# Laser_Array_CPU_V1_4.net
KiCad netlist of a schematic drawn in EAGLE
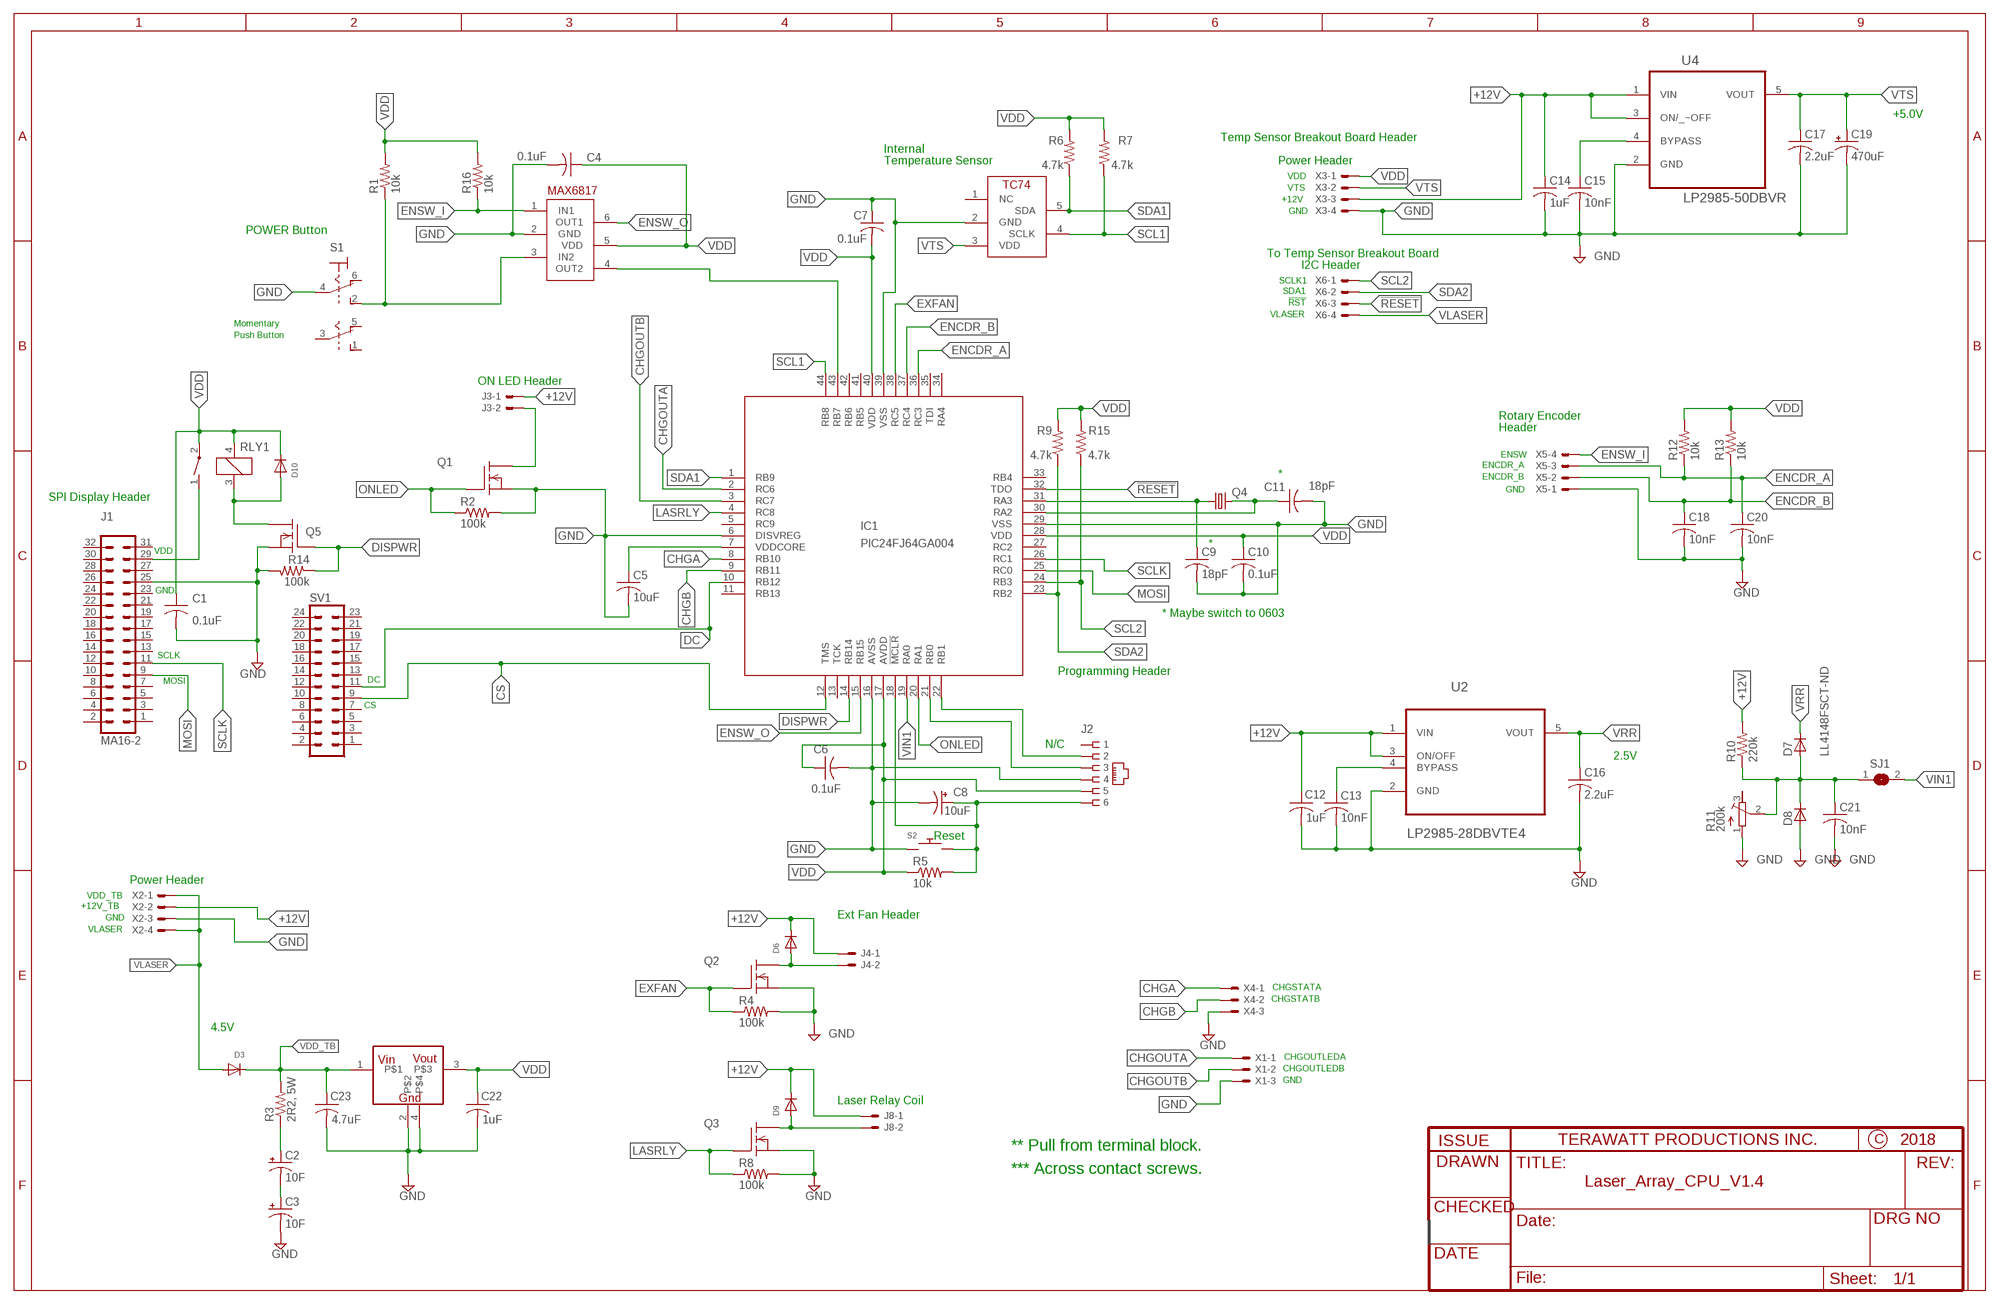
[diagram p0: schematic, sheet 1]

(export (version "E")
  (design (tool "Eeschema 10.0.6"))
  (components
    (comp (ref "C1")
      (value "0.1uF")
      (footprint "eagle-import:C0805")
      (libsource (lib "eagle-import") (part "C-USC0805"))
    )
    (comp (ref "C2")
      (value "10F")
      (footprint "eagle-import:E5-10,5")
      (libsource (lib "eagle-import") (part "CPOL-USE5-10.5"))
    )
    (comp (ref "C3")
      (value "10F")
      (footprint "eagle-import:E5-10,5")
      (libsource (lib "eagle-import") (part "CPOL-USE5-10.5"))
    )
    (comp (ref "C4")
      (value "0.1uF")
      (footprint "eagle-import:C0805")
      (libsource (lib "eagle-import") (part "C-USC0805"))
    )
    (comp (ref "C5")
      (value "10uF")
      (footprint "eagle-import:C0805")
      (libsource (lib "eagle-import") (part "C-USC0805"))
    )
    (comp (ref "C6")
      (value "0.1uF")
      (footprint "eagle-import:C0805")
      (libsource (lib "eagle-import") (part "C-USC0805"))
    )
    (comp (ref "C7")
      (value "0.1uF")
      (footprint "eagle-import:C0805")
      (libsource (lib "eagle-import") (part "C-USC0805"))
    )
    (comp (ref "C8")
      (value "10uF")
      (footprint "eagle-import:CAP3X3")
      (libsource (lib "eagle-import") (part "CAP3X3"))
    )
    (comp (ref "C9")
      (value "18pF")
      (footprint "eagle-import:C0805")
      (libsource (lib "eagle-import") (part "C-USC0805"))
    )
    (comp (ref "C10")
      (value "0.1uF")
      (footprint "eagle-import:C0805")
      (libsource (lib "eagle-import") (part "C-USC0805"))
    )
    (comp (ref "C11")
      (value "18pF")
      (footprint "eagle-import:C0805")
      (libsource (lib "eagle-import") (part "C-USC0805"))
    )
    (comp (ref "C12")
      (value "1uF")
      (footprint "eagle-import:C0805")
      (libsource (lib "eagle-import") (part "C-USC0805"))
    )
    (comp (ref "C13")
      (value "10nF")
      (footprint "eagle-import:C0805")
      (libsource (lib "eagle-import") (part "C-USC0805"))
    )
    (comp (ref "C14")
      (value "1uF")
      (footprint "eagle-import:C0805")
      (libsource (lib "eagle-import") (part "C-USC0805"))
    )
    (comp (ref "C15")
      (value "10nF")
      (footprint "eagle-import:C0805")
      (libsource (lib "eagle-import") (part "C-USC0805"))
    )
    (comp (ref "C16")
      (value "2.2uF")
      (footprint "eagle-import:C0805")
      (libsource (lib "eagle-import") (part "C-USC0805"))
    )
    (comp (ref "C17")
      (value "2.2uF")
      (footprint "eagle-import:C0805")
      (libsource (lib "eagle-import") (part "C-USC0805"))
    )
    (comp (ref "C18")
      (value "10nF")
      (footprint "eagle-import:C0805")
      (libsource (lib "eagle-import") (part "C-USC0805"))
    )
    (comp (ref "C19")
      (value "470uF")
      (footprint "eagle-import:PANASONIC_F")
      (libsource (lib "eagle-import") (part "CPOL-USF"))
    )
    (comp (ref "C20")
      (value "10nF")
      (footprint "eagle-import:C0805")
      (libsource (lib "eagle-import") (part "C-USC0805"))
    )
    (comp (ref "C21")
      (value "10nF")
      (footprint "eagle-import:C0805")
      (libsource (lib "eagle-import") (part "C-USC0805"))
    )
    (comp (ref "C22")
      (value "1uF")
      (footprint "eagle-import:C0805")
      (libsource (lib "eagle-import") (part "C-USC0805"))
    )
    (comp (ref "C23")
      (value "4.7uF")
      (footprint "eagle-import:C0805")
      (libsource (lib "eagle-import") (part "C-USC0805"))
    )
    (comp (ref "D3")
      (value "S10M-TPMSCT_ND")
      (footprint "eagle-import:S10M-TPMSCT-ND")
      (libsource (lib "eagle-import") (part "S10M-TPMSCT_ND"))
    )
    (comp (ref "D6")
      (value "DIODE_GENPURP_1A_100V")
      (footprint "eagle-import:DO214AC")
      (libsource (lib "eagle-import") (part "DIODE_GENPURP_1A_100V"))
    )
    (comp (ref "D7")
      (value "LL4148FSCT-ND")
      (footprint "eagle-import:SOD80")
      (libsource (lib "eagle-import") (part "D-SOD-80"))
    )
    (comp (ref "D8")
      (value "LL4148FSCT-ND")
      (footprint "eagle-import:SOD80")
      (libsource (lib "eagle-import") (part "D-SOD-80"))
    )
    (comp (ref "D9")
      (value "DIODE_GENPURP_1A_100V")
      (footprint "eagle-import:DO214AC")
      (libsource (lib "eagle-import") (part "DIODE_GENPURP_1A_100V"))
    )
    (comp (ref "D10")
      (value "DIODE_GENPURP_1A_100V")
      (footprint "eagle-import:DO214AC")
      (libsource (lib "eagle-import") (part "DIODE_GENPURP_1A_100V"))
    )
    (comp (ref "IC1")
      (value "PIC24FJ64GA004")
      (footprint "eagle-import:TQFP44")
      (fields (field (name "MPN") "PIC24FJ64GA004-E/PT"))
      (libsource (lib "eagle-import") (part "PIC24FJ64GA004"))
    )
    (comp (ref "J1")
      (value "MA16-2")
      (footprint "eagle-import:MA16-2")
      (libsource (lib "eagle-import") (part "MA16-2"))
    )
    (comp (ref "J2")
      (value "RJ_25")
      (footprint "eagle-import:RJ11-NO_SHIELD")
      (libsource (lib "eagle-import") (part "RJ_25"))
    )
    (comp (ref "J3")
      (value "22-23-2021")
      (footprint "eagle-import:22-23-2021")
      (fields (field (name "MF") "MOLEX"))
      (libsource (lib "eagle-import") (part "22-23-2021"))
    )
    (comp (ref "J4")
      (value "22-23-2021")
      (footprint "eagle-import:22-23-2021")
      (fields (field (name "MF") "MOLEX"))
      (libsource (lib "eagle-import") (part "22-23-2021"))
    )
    (comp (ref "J8")
      (value "22-23-2021")
      (footprint "eagle-import:22-23-2021")
      (fields (field (name "MF") "MOLEX"))
      (libsource (lib "eagle-import") (part "22-23-2021"))
    )
    (comp (ref "Q1")
      (value "QS5U34CT-ND_MOSFET_N_CHANNEL")
      (footprint "eagle-import:SOT23-5L")
      (libsource (lib "eagle-import") (part "QS5U34CT-ND_MOSFET_N_CHANNEL"))
    )
    (comp (ref "Q2")
      (value "QS5U34CT-ND_MOSFET_N_CHANNEL")
      (footprint "eagle-import:SOT23-5L")
      (libsource (lib "eagle-import") (part "QS5U34CT-ND_MOSFET_N_CHANNEL"))
    )
    (comp (ref "Q3")
      (value "QS5U34CT-ND_MOSFET_N_CHANNEL")
      (footprint "eagle-import:SOT23-5L")
      (libsource (lib "eagle-import") (part "QS5U34CT-ND_MOSFET_N_CHANNEL"))
    )
    (comp (ref "Q4")
      (value "CRYSTALSM49")
      (footprint "eagle-import:SM49")
      (libsource (lib "eagle-import") (part "CRYSTALSM49"))
    )
    (comp (ref "Q5")
      (value "QS5U34CT-ND_MOSFET_N_CHANNEL")
      (footprint "eagle-import:SOT23-5L")
      (libsource (lib "eagle-import") (part "QS5U34CT-ND_MOSFET_N_CHANNEL"))
    )
    (comp (ref "R1")
      (value "10k")
      (footprint "eagle-import:R0805")
      (libsource (lib "eagle-import") (part "R-US_R0805"))
    )
    (comp (ref "R2")
      (value "100k")
      (footprint "eagle-import:R0805")
      (libsource (lib "eagle-import") (part "R-US_R0805"))
    )
    (comp (ref "R3")
      (value "2R2, 5W")
      (footprint "eagle-import:RESISTOR5W")
      (libsource (lib "eagle-import") (part "RESISTOR5W"))
    )
    (comp (ref "R4")
      (value "100k")
      (footprint "eagle-import:R0805")
      (libsource (lib "eagle-import") (part "R-US_R0805"))
    )
    (comp (ref "R5")
      (value "10k")
      (footprint "eagle-import:R0805")
      (libsource (lib "eagle-import") (part "R-US_R0805"))
    )
    (comp (ref "R6")
      (value "4.7k")
      (footprint "eagle-import:M0805")
      (libsource (lib "eagle-import") (part "R-US_M0805"))
    )
    (comp (ref "R7")
      (value "4.7k")
      (footprint "eagle-import:M0805")
      (libsource (lib "eagle-import") (part "R-US_M0805"))
    )
    (comp (ref "R8")
      (value "100k")
      (footprint "eagle-import:R0805")
      (libsource (lib "eagle-import") (part "R-US_R0805"))
    )
    (comp (ref "R9")
      (value "4.7k")
      (footprint "eagle-import:M0805")
      (libsource (lib "eagle-import") (part "R-US_M0805"))
    )
    (comp (ref "R10")
      (value "220k")
      (footprint "eagle-import:M0805")
      (libsource (lib "eagle-import") (part "R-US_M0805"))
    )
    (comp (ref "R11")
      (value "200k")
      (footprint "eagle-import:RTRIM3224X")
      (libsource (lib "eagle-import") (part "R-TRIMM3224X"))
    )
    (comp (ref "R12")
      (value "10k")
      (footprint "eagle-import:M0805")
      (libsource (lib "eagle-import") (part "R-US_M0805"))
    )
    (comp (ref "R13")
      (value "10k")
      (footprint "eagle-import:M0805")
      (libsource (lib "eagle-import") (part "R-US_M0805"))
    )
    (comp (ref "R14")
      (value "100k")
      (footprint "eagle-import:R0805")
      (libsource (lib "eagle-import") (part "R-US_R0805"))
    )
    (comp (ref "R15")
      (value "4.7k")
      (footprint "eagle-import:M0805")
      (libsource (lib "eagle-import") (part "R-US_M0805"))
    )
    (comp (ref "R16")
      (value "10k")
      (footprint "eagle-import:R0805")
      (libsource (lib "eagle-import") (part "R-US_R0805"))
    )
    (comp (ref "RLY1")
      (value "RELAY_SPST_1A")
      (footprint "eagle-import:RELAY_SPST_1A")
      (libsource (lib "eagle-import") (part "RELAY_SPST_1A"))
    )
    (comp (ref "S1")
      (value "DPDT_TOGGLE")
      (footprint "eagle-import:22-23-2061")
      (libsource (lib "eagle-import") (part "DPDT_TOGGLE"))
    )
    (comp (ref "S2")
      (value "TACT_PB")
      (footprint "eagle-import:PUSHBUTTON_SMD_SJ")
      (libsource (lib "eagle-import") (part "TACT_PB"))
    )
    (comp (ref "S3")
      (value "TC74")
      (footprint "eagle-import:SOT23-5L")
      (libsource (lib "eagle-import") (part "TC74"))
    )
    (comp (ref "SJ1") (value "SJ") (footprint "eagle-import:SJ") (libsource (lib "eagle-import") (part "SJ")))
    (comp (ref "SV1")
      (value "MA12-2")
      (footprint "eagle-import:MA12-2")
      (libsource (lib "eagle-import") (part "MA12-2"))
    )
    (comp (ref "U1")
      (value "MAX6817")
      (footprint "eagle-import:SOT23-6")
      (libsource (lib "eagle-import") (part "MAX6817"))
    )
    (comp (ref "U2")
      (value "LP2985-28DBVTE4")
      (footprint "eagle-import:SOT95P280X145-5N")
      (libsource (lib "eagle-import") (part "LP2985-28DBVTE4"))
    )
    (comp (ref "U3")
      (value "V_REG_3.0V_1.0A")
      (footprint "eagle-import:SOT223")
      (libsource (lib "eagle-import") (part "V_REG_3.0V_1.0A"))
    )
    (comp (ref "U4")
      (value "LP2985-50DBVR")
      (footprint "eagle-import:SOT95P280X145-5N")
      (fields (field (name "MPN") "LP2985-33DBVT"))
      (libsource (lib "eagle-import") (part "LP2985-50DBVR"))
    )
    (comp (ref "X1")
      (value "22-23-2031")
      (footprint "eagle-import:22-23-2031")
      (fields (field (name "MF") "MOLEX"))
      (libsource (lib "eagle-import") (part "22-23-2031"))
    )
    (comp (ref "X2")
      (value "22-23-2041")
      (footprint "eagle-import:22-23-2041")
      (fields (field (name "MF") "MOLEX"))
      (libsource (lib "eagle-import") (part "22-23-2041"))
    )
    (comp (ref "X3")
      (value "22-23-2041")
      (footprint "eagle-import:22-23-2041")
      (fields (field (name "MF") "MOLEX"))
      (libsource (lib "eagle-import") (part "22-23-2041"))
    )
    (comp (ref "X4")
      (value "22-23-2031")
      (footprint "eagle-import:22-23-2031")
      (fields (field (name "MF") "MOLEX"))
      (libsource (lib "eagle-import") (part "22-23-2031"))
    )
    (comp (ref "X5")
      (value "22-23-2041")
      (footprint "eagle-import:22-23-2041")
      (fields (field (name "MF") "MOLEX"))
      (libsource (lib "eagle-import") (part "22-23-2041"))
    )
    (comp (ref "X6")
      (value "22-23-2041")
      (footprint "eagle-import:22-23-2041")
      (fields (field (name "MF") "MOLEX"))
      (libsource (lib "eagle-import") (part "22-23-2041"))
    )
  )
  (nets
    (net (code "1") (name "+12V") (class "Default")
      (node (ref "C12") (pin "1") (pinfunction "1_1") (pintype "passive"))
      (node (ref "C14") (pin "1") (pinfunction "1_1") (pintype "passive"))
      (node (ref "D6") (pin "C") (pinfunction "C_C") (pintype "passive"))
      (node (ref "D9") (pin "C") (pinfunction "C_C") (pintype "passive"))
      (node (ref "J3") (pin "1") (pinfunction "S_1") (pintype "passive"))
      (node (ref "J4") (pin "1") (pinfunction "S_1") (pintype "passive"))
      (node (ref "J8") (pin "1") (pinfunction "S_1") (pintype "passive"))
      (node (ref "R10") (pin "2") (pinfunction "2_2") (pintype "passive"))
      (node (ref "U2") (pin "1") (pinfunction "VIN_1") (pintype "power_in"))
      (node (ref "U2") (pin "3") (pinfunction "ON/OFF_3") (pintype "input"))
      (node (ref "U4") (pin "1") (pinfunction "VIN_1") (pintype "power_in"))
      (node (ref "U4") (pin "3") (pinfunction "ON/_~{OFF}_3") (pintype "input"))
      (node (ref "X2") (pin "2") (pinfunction "S_2") (pintype "passive"))
      (node (ref "X3") (pin "3") (pinfunction "S_3") (pintype "passive"))
    )
    (net (code "2") (name "/~{RESET}") (class "Default")
      (node (ref "IC1") (pin "32") (pinfunction "TDO_32") (pintype "output"))
      (node (ref "X6") (pin "3") (pinfunction "S_3") (pintype "passive"))
    )
    (net (code "3") (name "CHGA") (class "Default")
      (node (ref "IC1") (pin "8") (pinfunction "RB10_8") (pintype "bidirectional"))
      (node (ref "X4") (pin "1") (pinfunction "S_1") (pintype "passive"))
    )
    (net (code "4") (name "CHGB") (class "Default")
      (node (ref "IC1") (pin "9") (pinfunction "RB11_9") (pintype "bidirectional"))
      (node (ref "X4") (pin "2") (pinfunction "S_2") (pintype "passive"))
    )
    (net (code "5") (name "CHGOUTA") (class "Default")
      (node (ref "IC1") (pin "2") (pinfunction "RC6_2") (pintype "bidirectional"))
      (node (ref "X1") (pin "1") (pinfunction "S_1") (pintype "passive"))
    )
    (net (code "6") (name "CHGOUTB") (class "Default")
      (node (ref "IC1") (pin "3") (pinfunction "RC7_3") (pintype "bidirectional"))
      (node (ref "X1") (pin "2") (pinfunction "S_2") (pintype "passive"))
    )
    (net (code "7") (name "CS") (class "Default")
      (node (ref "IC1") (pin "12") (pinfunction "TMS_12") (pintype "input"))
      (node (ref "SV1") (pin "9") (pinfunction "9_9") (pintype "passive"))
    )
    (net (code "8") (name "DC") (class "Default")
      (node (ref "IC1") (pin "10") (pinfunction "RB12_10") (pintype "bidirectional"))
      (node (ref "SV1") (pin "11") (pinfunction "11_11") (pintype "passive"))
    )
    (net (code "9") (name "DISPWR") (class "Default")
      (node (ref "IC1") (pin "14") (pinfunction "RB14_14") (pintype "bidirectional"))
      (node (ref "Q5") (pin "1") (pinfunction "G_1") (pintype "passive"))
      (node (ref "R14") (pin "1") (pinfunction "1_1") (pintype "passive"))
    )
    (net (code "10") (name "ENCDR_A") (class "Default")
      (node (ref "C20") (pin "1") (pinfunction "1_1") (pintype "passive"))
      (node (ref "IC1") (pin "36") (pinfunction "RC3_36") (pintype "bidirectional"))
      (node (ref "R12") (pin "1") (pinfunction "1_1") (pintype "passive"))
      (node (ref "X5") (pin "3") (pinfunction "S_3") (pintype "passive"))
    )
    (net (code "11") (name "ENCDR_B") (class "Default")
      (node (ref "C18") (pin "1") (pinfunction "1_1") (pintype "passive"))
      (node (ref "IC1") (pin "37") (pinfunction "RC4_37") (pintype "bidirectional"))
      (node (ref "R13") (pin "1") (pinfunction "1_1") (pintype "passive"))
      (node (ref "X5") (pin "2") (pinfunction "S_2") (pintype "passive"))
    )
    (net (code "12") (name "ENSW_I") (class "Default")
      (node (ref "R16") (pin "1") (pinfunction "1_1") (pintype "passive"))
      (node (ref "U1") (pin "1") (pinfunction "IN1_1") (pintype "input"))
      (node (ref "X5") (pin "4") (pinfunction "S_4") (pintype "passive"))
    )
    (net (code "13") (name "ENSW_O") (class "Default")
      (node (ref "IC1") (pin "15") (pinfunction "RB15_15") (pintype "bidirectional"))
      (node (ref "U1") (pin "6") (pinfunction "OUT1_6") (pintype "output"))
    )
    (net (code "14") (name "EXFAN") (class "Default")
      (node (ref "IC1") (pin "38") (pinfunction "RC5_38") (pintype "bidirectional"))
      (node (ref "Q2") (pin "1") (pinfunction "G_1") (pintype "passive"))
      (node (ref "R4") (pin "1") (pinfunction "1_1") (pintype "passive"))
    )
    (net (code "15") (name "GND") (class "Default")
      (node (ref "C1") (pin "2") (pinfunction "2_2") (pintype "passive"))
      (node (ref "C10") (pin "2") (pinfunction "2_2") (pintype "passive"))
      (node (ref "C11") (pin "2") (pinfunction "2_2") (pintype "passive"))
      (node (ref "C12") (pin "2") (pinfunction "2_2") (pintype "passive"))
      (node (ref "C13") (pin "2") (pinfunction "2_2") (pintype "passive"))
      (node (ref "C14") (pin "2") (pinfunction "2_2") (pintype "passive"))
      (node (ref "C15") (pin "2") (pinfunction "2_2") (pintype "passive"))
      (node (ref "C16") (pin "2") (pinfunction "2_2") (pintype "passive"))
      (node (ref "C17") (pin "2") (pinfunction "2_2") (pintype "passive"))
      (node (ref "C18") (pin "2") (pinfunction "2_2") (pintype "passive"))
      (node (ref "C19") (pin "-") (pinfunction "-_-") (pintype "passive"))
      (node (ref "C20") (pin "2") (pinfunction "2_2") (pintype "passive"))
      (node (ref "C21") (pin "2") (pinfunction "2_2") (pintype "passive"))
      (node (ref "C22") (pin "2") (pinfunction "2_2") (pintype "passive"))
      (node (ref "C23") (pin "2") (pinfunction "2_2") (pintype "passive"))
      (node (ref "C3") (pin "-") (pinfunction "-_-") (pintype "passive"))
      (node (ref "C4") (pin "2") (pinfunction "2_2") (pintype "passive"))
      (node (ref "C5") (pin "2") (pinfunction "2_2") (pintype "passive"))
      (node (ref "C6") (pin "2") (pinfunction "2_2") (pintype "passive"))
      (node (ref "C7") (pin "1") (pinfunction "1_1") (pintype "passive"))
      (node (ref "C8") (pin "-") (pinfunction "-_-") (pintype "passive"))
      (node (ref "C9") (pin "2") (pinfunction "2_2") (pintype "passive"))
      (node (ref "D8") (pin "2") (pinfunction "A_2") (pintype "passive"))
      (node (ref "IC1") (pin "16") (pinfunction "AVSS_16") (pintype "power_in"))
      (node (ref "IC1") (pin "29") (pinfunction "VSS_29") (pintype "power_in"))
      (node (ref "IC1") (pin "39") (pinfunction "VSS_39") (pintype "power_in"))
      (node (ref "IC1") (pin "6") (pinfunction "DISVREG_6") (pintype "passive"))
      (node (ref "J1") (pin "25") (pinfunction "25_25") (pintype "passive"))
      (node (ref "J2") (pin "4") (pinfunction "4_4") (pintype "passive"))
      (node (ref "Q1") (pin "2") (pinfunction "S_2") (pintype "passive"))
      (node (ref "Q2") (pin "2") (pinfunction "S_2") (pintype "passive"))
      (node (ref "Q3") (pin "2") (pinfunction "S_2") (pintype "passive"))
      (node (ref "Q5") (pin "2") (pinfunction "S_2") (pintype "passive"))
      (node (ref "R11") (pin "1") (pinfunction "A_1") (pintype "passive"))
      (node (ref "R14") (pin "2") (pinfunction "2_2") (pintype "passive"))
      (node (ref "R2") (pin "2") (pinfunction "2_2") (pintype "passive"))
      (node (ref "R4") (pin "2") (pinfunction "2_2") (pintype "passive"))
      (node (ref "R8") (pin "2") (pinfunction "2_2") (pintype "passive"))
      (node (ref "S1") (pin "4") (pinfunction "P_4") (pintype "passive"))
      (node (ref "S2") (pin "1") (pinfunction "1_1") (pintype "passive"))
      (node (ref "S2") (pin "2") (pinfunction "1_2") (pintype "passive"))
      (node (ref "S3") (pin "2") (pinfunction "GND_2") (pintype "bidirectional"))
      (node (ref "U1") (pin "2") (pinfunction "GND_2") (pintype "power_in"))
      (node (ref "U2") (pin "2") (pinfunction "GND_2") (pintype "passive"))
      (node (ref "U3") (pin "2") (pinfunction "P$2_2") (pintype "bidirectional"))
      (node (ref "U3") (pin "4") (pinfunction "P$4_4") (pintype "bidirectional"))
      (node (ref "U4") (pin "2") (pinfunction "GND_2") (pintype "passive"))
      (node (ref "X1") (pin "3") (pinfunction "S_3") (pintype "passive"))
      (node (ref "X2") (pin "3") (pinfunction "S_3") (pintype "passive"))
      (node (ref "X3") (pin "4") (pinfunction "S_4") (pintype "passive"))
      (node (ref "X4") (pin "3") (pinfunction "S_3") (pintype "passive"))
      (node (ref "X5") (pin "1") (pinfunction "S_1") (pintype "passive"))
    )
    (net (code "16") (name "LASRLY") (class "Default")
      (node (ref "IC1") (pin "4") (pinfunction "RC8_4") (pintype "bidirectional"))
      (node (ref "Q3") (pin "1") (pinfunction "G_1") (pintype "passive"))
      (node (ref "R8") (pin "1") (pinfunction "1_1") (pintype "passive"))
    )
    (net (code "17") (name "MOSI") (class "Default")
      (node (ref "IC1") (pin "25") (pinfunction "RC0_25") (pintype "bidirectional"))
      (node (ref "J1") (pin "9") (pinfunction "9_9") (pintype "passive"))
    )
    (net (code "18") (name "Net-(C2-Pad+)") (class "Default")
      (node (ref "C2") (pin "+") (pinfunction "+_+") (pintype "passive"))
      (node (ref "R3") (pin "1") (pinfunction "1_1") (pintype "passive"))
    )
    (net (code "19") (name "Net-(C2-Pad-)") (class "Default")
      (node (ref "C2") (pin "-") (pinfunction "-_-") (pintype "passive"))
      (node (ref "C3") (pin "+") (pinfunction "+_+") (pintype "passive"))
    )
    (net (code "20") (name "Net-(IC1-RA2)") (class "Default")
      (node (ref "C11") (pin "1") (pinfunction "1_1") (pintype "passive"))
      (node (ref "IC1") (pin "30") (pinfunction "RA2_30") (pintype "bidirectional"))
      (node (ref "Q4") (pin "2") (pinfunction "2_2") (pintype "passive"))
    )
    (net (code "21") (name "Net-(IC1-RA3)") (class "Default")
      (node (ref "C9") (pin "1") (pinfunction "1_1") (pintype "passive"))
      (node (ref "IC1") (pin "31") (pinfunction "RA3_31") (pintype "bidirectional"))
      (node (ref "Q4") (pin "1") (pinfunction "1_1") (pintype "passive"))
    )
    (net (code "22") (name "Net-(IC1-RB0)") (class "Default")
      (node (ref "IC1") (pin "21") (pinfunction "RB0_21") (pintype "bidirectional"))
      (node (ref "J2") (pin "3") (pinfunction "3_3") (pintype "passive"))
    )
    (net (code "23") (name "Net-(IC1-RB1)") (class "Default")
      (node (ref "IC1") (pin "22") (pinfunction "RB1_22") (pintype "bidirectional"))
      (node (ref "J2") (pin "2") (pinfunction "2_2") (pintype "passive"))
    )
    (net (code "24") (name "Net-(IC1-RB7)") (class "Default")
      (node (ref "IC1") (pin "43") (pinfunction "RB7_43") (pintype "bidirectional"))
      (node (ref "U1") (pin "4") (pinfunction "OUT2_4") (pintype "output"))
    )
    (net (code "25") (name "Net-(IC1-VDDCORE)") (class "Default")
      (node (ref "C5") (pin "1") (pinfunction "1_1") (pintype "passive"))
      (node (ref "IC1") (pin "7") (pinfunction "VDDCORE_7") (pintype "power_in"))
    )
    (net (code "26") (name "Net-(IC1-~{MCLR})") (class "Default")
      (node (ref "C8") (pin "+") (pinfunction "+_+") (pintype "passive"))
      (node (ref "IC1") (pin "18") (pinfunction "~{MCLR}_18") (pintype "bidirectional"))
      (node (ref "J2") (pin "6") (pinfunction "6_6") (pintype "passive"))
      (node (ref "R5") (pin "2") (pinfunction "2_2") (pintype "passive"))
      (node (ref "S2") (pin "3") (pinfunction "2_3") (pintype "passive"))
      (node (ref "S2") (pin "4") (pinfunction "2_4") (pintype "passive"))
    )
    (net (code "27") (name "Net-(J3B-S)") (class "Default")
      (node (ref "J3") (pin "2") (pinfunction "S_2") (pintype "passive"))
      (node (ref "Q1") (pin "5") (pinfunction "D_5") (pintype "passive"))
    )
    (net (code "28") (name "Net-(J4B-S)") (class "Default")
      (node (ref "D6") (pin "A") (pinfunction "A_A") (pintype "passive"))
      (node (ref "J4") (pin "2") (pinfunction "S_2") (pintype "passive"))
      (node (ref "Q2") (pin "5") (pinfunction "D_5") (pintype "passive"))
    )
    (net (code "29") (name "Net-(J8B-S)") (class "Default")
      (node (ref "D9") (pin "A") (pinfunction "A_A") (pintype "passive"))
      (node (ref "J8") (pin "2") (pinfunction "S_2") (pintype "passive"))
      (node (ref "Q3") (pin "5") (pinfunction "D_5") (pintype "passive"))
    )
    (net (code "30") (name "Net-(Q5-D)") (class "Default")
      (node (ref "D10") (pin "A") (pinfunction "A_A") (pintype "passive"))
      (node (ref "Q5") (pin "5") (pinfunction "D_5") (pintype "passive"))
      (node (ref "RLY1") (pin "3") (pinfunction "1_3") (pintype "passive"))
    )
    (net (code "31") (name "Net-(RLY1B-S)") (class "Default")
      (node (ref "J1") (pin "29") (pinfunction "29_29") (pintype "passive"))
      (node (ref "RLY1") (pin "1") (pinfunction "S_1") (pintype "passive"))
    )
    (net (code "32") (name "Net-(S1-S)") (class "Default")
      (node (ref "R1") (pin "1") (pinfunction "1_1") (pintype "passive"))
      (node (ref "S1") (pin "2") (pinfunction "S_2") (pintype "passive"))
      (node (ref "U1") (pin "3") (pinfunction "IN2_3") (pintype "input"))
    )
    (net (code "33") (name "Net-(U2-BYPASS)") (class "Default")
      (node (ref "C13") (pin "1") (pinfunction "1_1") (pintype "passive"))
      (node (ref "U2") (pin "4") (pinfunction "BYPASS_4") (pintype "input"))
    )
    (net (code "34") (name "Net-(U4-BYPASS)") (class "Default")
      (node (ref "C15") (pin "1") (pinfunction "1_1") (pintype "passive"))
      (node (ref "U4") (pin "4") (pinfunction "BYPASS_4") (pintype "input"))
    )
    (net (code "35") (name "ONLED") (class "Default")
      (node (ref "IC1") (pin "20") (pinfunction "RA1_20") (pintype "bidirectional"))
      (node (ref "Q1") (pin "1") (pinfunction "G_1") (pintype "passive"))
      (node (ref "R2") (pin "1") (pinfunction "1_1") (pintype "passive"))
    )
    (net (code "36") (name "SCL1") (class "Default")
      (node (ref "IC1") (pin "44") (pinfunction "RB8_44") (pintype "bidirectional"))
      (node (ref "R7") (pin "1") (pinfunction "1_1") (pintype "passive"))
      (node (ref "S3") (pin "4") (pinfunction "SCLK_4") (pintype "bidirectional"))
    )
    (net (code "37") (name "SCL2") (class "Default")
      (node (ref "IC1") (pin "24") (pinfunction "RB3_24") (pintype "bidirectional"))
      (node (ref "R15") (pin "1") (pinfunction "1_1") (pintype "passive"))
      (node (ref "X6") (pin "1") (pinfunction "S_1") (pintype "passive"))
    )
    (net (code "38") (name "SCLK") (class "Default")
      (node (ref "IC1") (pin "26") (pinfunction "RC1_26") (pintype "bidirectional"))
      (node (ref "J1") (pin "11") (pinfunction "11_11") (pintype "passive"))
    )
    (net (code "39") (name "SDA1") (class "Default")
      (node (ref "IC1") (pin "1") (pinfunction "RB9_1") (pintype "bidirectional"))
      (node (ref "R6") (pin "1") (pinfunction "1_1") (pintype "passive"))
      (node (ref "S3") (pin "5") (pinfunction "SDA_5") (pintype "bidirectional"))
    )
    (net (code "40") (name "SDA2") (class "Default")
      (node (ref "IC1") (pin "23") (pinfunction "RB2_23") (pintype "bidirectional"))
      (node (ref "R9") (pin "1") (pinfunction "1_1") (pintype "passive"))
      (node (ref "X6") (pin "2") (pinfunction "S_2") (pintype "passive"))
    )
    (net (code "41") (name "VDD") (class "Default")
      (node (ref "C1") (pin "1") (pinfunction "1_1") (pintype "passive"))
      (node (ref "C10") (pin "1") (pinfunction "1_1") (pintype "passive"))
      (node (ref "C22") (pin "1") (pinfunction "1_1") (pintype "passive"))
      (node (ref "C4") (pin "1") (pinfunction "1_1") (pintype "passive"))
      (node (ref "C6") (pin "1") (pinfunction "1_1") (pintype "passive"))
      (node (ref "C7") (pin "2") (pinfunction "2_2") (pintype "passive"))
      (node (ref "D10") (pin "C") (pinfunction "C_C") (pintype "passive"))
      (node (ref "IC1") (pin "17") (pinfunction "AVDD_17") (pintype "power_in"))
      (node (ref "IC1") (pin "28") (pinfunction "VDD_28") (pintype "power_in"))
      (node (ref "IC1") (pin "40") (pinfunction "VDD_40") (pintype "power_in"))
      (node (ref "J2") (pin "5") (pinfunction "5_5") (pintype "passive"))
      (node (ref "R1") (pin "2") (pinfunction "2_2") (pintype "passive"))
      (node (ref "R12") (pin "2") (pinfunction "2_2") (pintype "passive"))
      (node (ref "R13") (pin "2") (pinfunction "2_2") (pintype "passive"))
      (node (ref "R15") (pin "2") (pinfunction "2_2") (pintype "passive"))
      (node (ref "R16") (pin "2") (pinfunction "2_2") (pintype "passive"))
      (node (ref "R5") (pin "1") (pinfunction "1_1") (pintype "passive"))
      (node (ref "R6") (pin "2") (pinfunction "2_2") (pintype "passive"))
      (node (ref "R7") (pin "2") (pinfunction "2_2") (pintype "passive"))
      (node (ref "R9") (pin "2") (pinfunction "2_2") (pintype "passive"))
      (node (ref "RLY1") (pin "2") (pinfunction "P_2") (pintype "passive"))
      (node (ref "RLY1") (pin "4") (pinfunction "2_4") (pintype "passive"))
      (node (ref "U1") (pin "5") (pinfunction "VDD_5") (pintype "power_in"))
      (node (ref "U3") (pin "3") (pinfunction "P$3_3") (pintype "bidirectional"))
      (node (ref "X3") (pin "1") (pinfunction "S_1") (pintype "passive"))
    )
    (net (code "42") (name "VDD_TB") (class "Default")
      (node (ref "C23") (pin "1") (pinfunction "1_1") (pintype "passive"))
      (node (ref "D3") (pin "C") (pinfunction "C_C") (pintype "passive"))
      (node (ref "R3") (pin "2") (pinfunction "2_2") (pintype "passive"))
      (node (ref "U3") (pin "1") (pinfunction "P$1_1") (pintype "bidirectional"))
    )
    (net (code "43") (name "VIN1") (class "Default")
      (node (ref "C21") (pin "1") (pinfunction "1_1") (pintype "passive"))
      (node (ref "D7") (pin "2") (pinfunction "A_2") (pintype "passive"))
      (node (ref "D8") (pin "1") (pinfunction "C_1") (pintype "passive"))
      (node (ref "IC1") (pin "19") (pinfunction "RA0_19") (pintype "bidirectional"))
      (node (ref "R10") (pin "1") (pinfunction "1_1") (pintype "passive"))
      (node (ref "R11") (pin "2") (pinfunction "S_2") (pintype "passive"))
      (node (ref "SJ1") (pin "1") (pinfunction "1_1") (pintype "passive"))
      (node (ref "SJ1") (pin "2") (pinfunction "2_2") (pintype "passive"))
    )
    (net (code "44") (name "VLASER") (class "Default")
      (node (ref "D3") (pin "A") (pinfunction "A_A") (pintype "passive"))
      (node (ref "X2") (pin "1") (pinfunction "S_1") (pintype "passive"))
      (node (ref "X2") (pin "4") (pinfunction "S_4") (pintype "passive"))
      (node (ref "X6") (pin "4") (pinfunction "S_4") (pintype "passive"))
    )
    (net (code "45") (name "VRR") (class "Default")
      (node (ref "C16") (pin "1") (pinfunction "1_1") (pintype "passive"))
      (node (ref "D7") (pin "1") (pinfunction "C_1") (pintype "passive"))
      (node (ref "U2") (pin "5") (pinfunction "VOUT_5") (pintype "output"))
    )
    (net (code "46") (name "VTS") (class "Default")
      (node (ref "C17") (pin "1") (pinfunction "1_1") (pintype "passive"))
      (node (ref "C19") (pin "+") (pinfunction "+_+") (pintype "passive"))
      (node (ref "S3") (pin "3") (pinfunction "VDD_3") (pintype "bidirectional"))
      (node (ref "U4") (pin "5") (pinfunction "VOUT_5") (pintype "output"))
      (node (ref "X3") (pin "2") (pinfunction "S_2") (pintype "passive"))
    )
    (net (code "47") (name "unconnected-(IC1-RA4-Pad34)") (class "Default")
      (node (ref "IC1") (pin "34") (pinfunction "RA4_34") (pintype "bidirectional"))
    )
    (net (code "48") (name "unconnected-(IC1-RB4-Pad33)") (class "Default")
      (node (ref "IC1") (pin "33") (pinfunction "RB4_33") (pintype "bidirectional"))
    )
    (net (code "49") (name "unconnected-(IC1-RB5-Pad41)") (class "Default")
      (node (ref "IC1") (pin "41") (pinfunction "RB5_41") (pintype "bidirectional"))
    )
    (net (code "50") (name "unconnected-(IC1-RB6-Pad42)") (class "Default")
      (node (ref "IC1") (pin "42") (pinfunction "RB6_42") (pintype "bidirectional"))
    )
    (net (code "51") (name "unconnected-(IC1-RB13-Pad11)") (class "Default")
      (node (ref "IC1") (pin "11") (pinfunction "RB13_11") (pintype "bidirectional"))
    )
    (net (code "52") (name "unconnected-(IC1-RC2-Pad27)") (class "Default")
      (node (ref "IC1") (pin "27") (pinfunction "RC2_27") (pintype "bidirectional"))
    )
    (net (code "53") (name "unconnected-(IC1-RC9-Pad5)") (class "Default")
      (node (ref "IC1") (pin "5") (pinfunction "RC9_5") (pintype "bidirectional"))
    )
    (net (code "54") (name "unconnected-(IC1-TCK-Pad13)") (class "Default")
      (node (ref "IC1") (pin "13") (pinfunction "TCK_13") (pintype "input"))
    )
    (net (code "55") (name "unconnected-(IC1-TDI-Pad35)") (class "Default")
      (node (ref "IC1") (pin "35") (pinfunction "TDI_35") (pintype "input"))
    )
    (net (code "56") (name "unconnected-(J1-Pad1)") (class "Default")
      (node (ref "J1") (pin "1") (pinfunction "1_1") (pintype "passive"))
    )
    (net (code "57") (name "unconnected-(J1-Pad2)") (class "Default")
      (node (ref "J1") (pin "2") (pinfunction "2_2") (pintype "passive"))
    )
    (net (code "58") (name "unconnected-(J1-Pad3)") (class "Default")
      (node (ref "J1") (pin "3") (pinfunction "3_3") (pintype "passive"))
    )
    (net (code "59") (name "unconnected-(J1-Pad4)") (class "Default")
      (node (ref "J1") (pin "4") (pinfunction "4_4") (pintype "passive"))
    )
    (net (code "60") (name "unconnected-(J1-Pad5)") (class "Default")
      (node (ref "J1") (pin "5") (pinfunction "5_5") (pintype "passive"))
    )
    (net (code "61") (name "unconnected-(J1-Pad6)") (class "Default")
      (node (ref "J1") (pin "6") (pinfunction "6_6") (pintype "passive"))
    )
    (net (code "62") (name "unconnected-(J1-Pad7)") (class "Default")
      (node (ref "J1") (pin "7") (pinfunction "7_7") (pintype "passive"))
    )
    (net (code "63") (name "unconnected-(J1-Pad8)") (class "Default")
      (node (ref "J1") (pin "8") (pinfunction "8_8") (pintype "passive"))
    )
    (net (code "64") (name "unconnected-(J1-Pad10)") (class "Default")
      (node (ref "J1") (pin "10") (pinfunction "10_10") (pintype "passive"))
    )
    (net (code "65") (name "unconnected-(J1-Pad12)") (class "Default")
      (node (ref "J1") (pin "12") (pinfunction "12_12") (pintype "passive"))
    )
    (net (code "66") (name "unconnected-(J1-Pad13)") (class "Default")
      (node (ref "J1") (pin "13") (pinfunction "13_13") (pintype "passive"))
    )
    (net (code "67") (name "unconnected-(J1-Pad14)") (class "Default")
      (node (ref "J1") (pin "14") (pinfunction "14_14") (pintype "passive"))
    )
    (net (code "68") (name "unconnected-(J1-Pad15)") (class "Default")
      (node (ref "J1") (pin "15") (pinfunction "15_15") (pintype "passive"))
    )
    (net (code "69") (name "unconnected-(J1-Pad16)") (class "Default")
      (node (ref "J1") (pin "16") (pinfunction "16_16") (pintype "passive"))
    )
    (net (code "70") (name "unconnected-(J1-Pad17)") (class "Default")
      (node (ref "J1") (pin "17") (pinfunction "17_17") (pintype "passive"))
    )
    (net (code "71") (name "unconnected-(J1-Pad18)") (class "Default")
      (node (ref "J1") (pin "18") (pinfunction "18_18") (pintype "passive"))
    )
    (net (code "72") (name "unconnected-(J1-Pad19)") (class "Default")
      (node (ref "J1") (pin "19") (pinfunction "19_19") (pintype "passive"))
    )
    (net (code "73") (name "unconnected-(J1-Pad20)") (class "Default")
      (node (ref "J1") (pin "20") (pinfunction "20_20") (pintype "passive"))
    )
    (net (code "74") (name "unconnected-(J1-Pad21)") (class "Default")
      (node (ref "J1") (pin "21") (pinfunction "21_21") (pintype "passive"))
    )
    (net (code "75") (name "unconnected-(J1-Pad22)") (class "Default")
      (node (ref "J1") (pin "22") (pinfunction "22_22") (pintype "passive"))
    )
    (net (code "76") (name "unconnected-(J1-Pad23)") (class "Default")
      (node (ref "J1") (pin "23") (pinfunction "23_23") (pintype "passive"))
    )
    (net (code "77") (name "unconnected-(J1-Pad24)") (class "Default")
      (node (ref "J1") (pin "24") (pinfunction "24_24") (pintype "passive"))
    )
    (net (code "78") (name "unconnected-(J1-Pad26)") (class "Default")
      (node (ref "J1") (pin "26") (pinfunction "26_26") (pintype "passive"))
    )
    (net (code "79") (name "unconnected-(J1-Pad27)") (class "Default")
      (node (ref "J1") (pin "27") (pinfunction "27_27") (pintype "passive"))
    )
    (net (code "80") (name "unconnected-(J1-Pad28)") (class "Default")
      (node (ref "J1") (pin "28") (pinfunction "28_28") (pintype "passive"))
    )
    (net (code "81") (name "unconnected-(J1-Pad30)") (class "Default")
      (node (ref "J1") (pin "30") (pinfunction "30_30") (pintype "passive"))
    )
    (net (code "82") (name "unconnected-(J1-Pad31)") (class "Default")
      (node (ref "J1") (pin "31") (pinfunction "31_31") (pintype "passive"))
    )
    (net (code "83") (name "unconnected-(J1-Pad32)") (class "Default")
      (node (ref "J1") (pin "32") (pinfunction "32_32") (pintype "passive"))
    )
    (net (code "84") (name "unconnected-(J2-Pad1)") (class "Default")
      (node (ref "J2") (pin "1") (pinfunction "1_1") (pintype "passive"))
    )
    (net (code "85") (name "unconnected-(R11-E-Pad3)") (class "Default")
      (node (ref "R11") (pin "3") (pinfunction "E_3") (pintype "passive"))
    )
    (net (code "86") (name "unconnected-(S1-O-Pad6)") (class "Default")
      (node (ref "S1") (pin "6") (pinfunction "O_6") (pintype "passive"))
    )
    (net (code "87") (name "unconnected-(S1-O1-Pad5)") (class "Default")
      (node (ref "S1") (pin "5") (pinfunction "O1_5") (pintype "passive"))
    )
    (net (code "88") (name "unconnected-(S1-P1-Pad3)") (class "Default")
      (node (ref "S1") (pin "3") (pinfunction "P1_3") (pintype "passive"))
    )
    (net (code "89") (name "unconnected-(S1-S1-Pad1)") (class "Default")
      (node (ref "S1") (pin "1") (pinfunction "S1_1") (pintype "passive"))
    )
    (net (code "90") (name "unconnected-(S3-NC-Pad1)") (class "Default")
      (node (ref "S3") (pin "1") (pinfunction "NC_1") (pintype "bidirectional"))
    )
    (net (code "91") (name "unconnected-(SV1-Pad1)") (class "Default")
      (node (ref "SV1") (pin "1") (pinfunction "1_1") (pintype "passive"))
    )
    (net (code "92") (name "unconnected-(SV1-Pad2)") (class "Default")
      (node (ref "SV1") (pin "2") (pinfunction "2_2") (pintype "passive"))
    )
    (net (code "93") (name "unconnected-(SV1-Pad3)") (class "Default")
      (node (ref "SV1") (pin "3") (pinfunction "3_3") (pintype "passive"))
    )
    (net (code "94") (name "unconnected-(SV1-Pad4)") (class "Default")
      (node (ref "SV1") (pin "4") (pinfunction "4_4") (pintype "passive"))
    )
    (net (code "95") (name "unconnected-(SV1-Pad5)") (class "Default")
      (node (ref "SV1") (pin "5") (pinfunction "5_5") (pintype "passive"))
    )
    (net (code "96") (name "unconnected-(SV1-Pad6)") (class "Default")
      (node (ref "SV1") (pin "6") (pinfunction "6_6") (pintype "passive"))
    )
    (net (code "97") (name "unconnected-(SV1-Pad7)") (class "Default")
      (node (ref "SV1") (pin "7") (pinfunction "7_7") (pintype "passive"))
    )
    (net (code "98") (name "unconnected-(SV1-Pad8)") (class "Default")
      (node (ref "SV1") (pin "8") (pinfunction "8_8") (pintype "passive"))
    )
    (net (code "99") (name "unconnected-(SV1-Pad10)") (class "Default")
      (node (ref "SV1") (pin "10") (pinfunction "10_10") (pintype "passive"))
    )
    (net (code "100") (name "unconnected-(SV1-Pad12)") (class "Default")
      (node (ref "SV1") (pin "12") (pinfunction "12_12") (pintype "passive"))
    )
    (net (code "101") (name "unconnected-(SV1-Pad13)") (class "Default")
      (node (ref "SV1") (pin "13") (pinfunction "13_13") (pintype "passive"))
    )
    (net (code "102") (name "unconnected-(SV1-Pad14)") (class "Default")
      (node (ref "SV1") (pin "14") (pinfunction "14_14") (pintype "passive"))
    )
    (net (code "103") (name "unconnected-(SV1-Pad15)") (class "Default")
      (node (ref "SV1") (pin "15") (pinfunction "15_15") (pintype "passive"))
    )
    (net (code "104") (name "unconnected-(SV1-Pad16)") (class "Default")
      (node (ref "SV1") (pin "16") (pinfunction "16_16") (pintype "passive"))
    )
    (net (code "105") (name "unconnected-(SV1-Pad17)") (class "Default")
      (node (ref "SV1") (pin "17") (pinfunction "17_17") (pintype "passive"))
    )
    (net (code "106") (name "unconnected-(SV1-Pad18)") (class "Default")
      (node (ref "SV1") (pin "18") (pinfunction "18_18") (pintype "passive"))
    )
    (net (code "107") (name "unconnected-(SV1-Pad19)") (class "Default")
      (node (ref "SV1") (pin "19") (pinfunction "19_19") (pintype "passive"))
    )
    (net (code "108") (name "unconnected-(SV1-Pad20)") (class "Default")
      (node (ref "SV1") (pin "20") (pinfunction "20_20") (pintype "passive"))
    )
    (net (code "109") (name "unconnected-(SV1-Pad21)") (class "Default")
      (node (ref "SV1") (pin "21") (pinfunction "21_21") (pintype "passive"))
    )
    (net (code "110") (name "unconnected-(SV1-Pad22)") (class "Default")
      (node (ref "SV1") (pin "22") (pinfunction "22_22") (pintype "passive"))
    )
    (net (code "111") (name "unconnected-(SV1-Pad23)") (class "Default")
      (node (ref "SV1") (pin "23") (pinfunction "23_23") (pintype "passive"))
    )
    (net (code "112") (name "unconnected-(SV1-Pad24)") (class "Default")
      (node (ref "SV1") (pin "24") (pinfunction "24_24") (pintype "passive"))
    )
  )
)
